# ServoEncoder_Serial.net
KiCad netlist of a schematic drawn in EAGLE
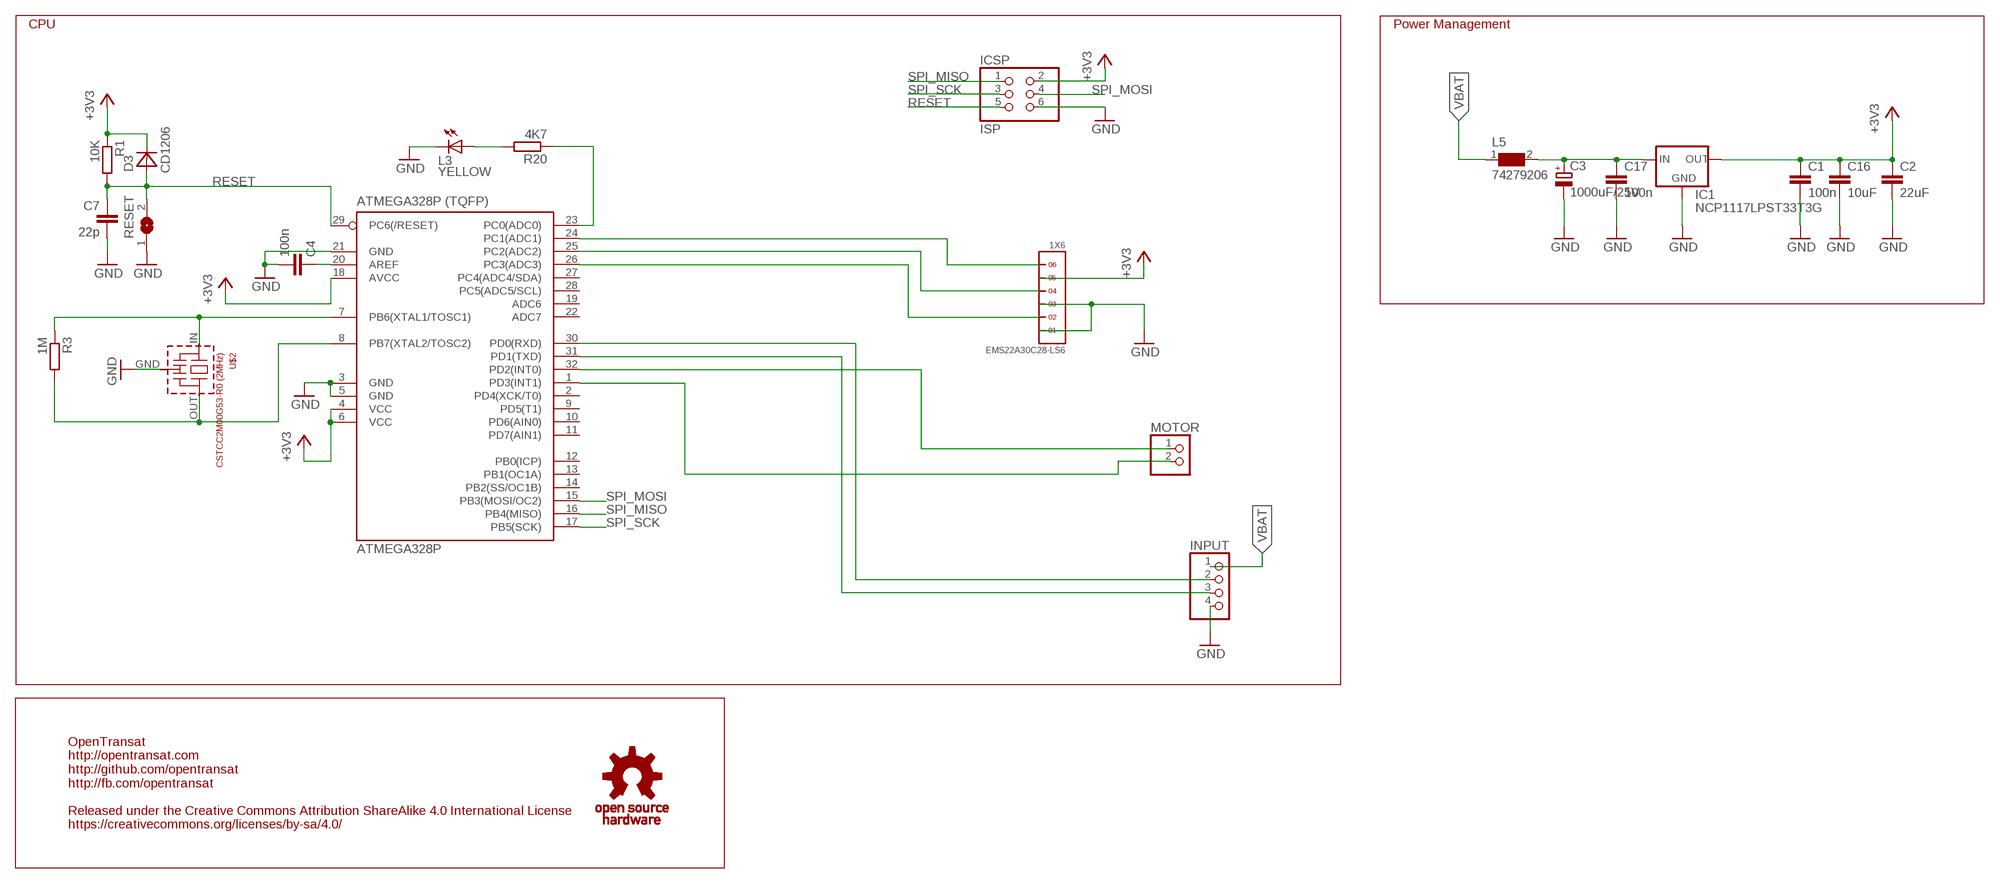
[diagram p0: schematic, sheet 1]

(export (version "E")
  (design (tool "Eeschema 10.0.6"))
  (components
    (comp (ref "ATMEGA328P")
      (value "ATMEGA328P (TQFP)")
      (footprint "eagle-import:TQFP32-08")
      (fields (field (name "MPN") "ATMEGA8-16AU"))
      (libsource (lib "eagle-import") (part "MEGA8-AI"))
    )
    (comp (ref "C1")
      (value "100n")
      (footprint "eagle-import:C0603")
      (libsource (lib "eagle-import") (part "C-EUC0603"))
    )
    (comp (ref "C2")
      (value "22uF")
      (footprint "eagle-import:C1210")
      (libsource (lib "eagle-import") (part "C-EUC1210"))
    )
    (comp (ref "C3")
      (value "1000uF/25V")
      (footprint "eagle-import:E5-10,5")
      (libsource (lib "eagle-import") (part "CPOL-EUE5-10.5"))
    )
    (comp (ref "C4")
      (value "100n")
      (footprint "eagle-import:C0603")
      (libsource (lib "eagle-import") (part "C-EUC0603"))
    )
    (comp (ref "C7")
      (value "22p")
      (footprint "eagle-import:C0603")
      (libsource (lib "eagle-import") (part "C-EUC0603"))
    )
    (comp (ref "C16")
      (value "10uF")
      (footprint "eagle-import:C1206")
      (libsource (lib "eagle-import") (part "C-EUC1206"))
    )
    (comp (ref "C17")
      (value "100n")
      (footprint "eagle-import:C0603")
      (libsource (lib "eagle-import") (part "C-EUC0603"))
    )
    (comp (ref "D3")
      (value "CD1206")
      (footprint "eagle-import:R1206")
      (libsource (lib "eagle-import") (part "CD1206"))
    )
    (comp (ref "EMS22A30C28-LS6")
      (value "1X6")
      (footprint "eagle-import:1X6")
      (libsource (lib "eagle-import") (part "1X6"))
    )
    (comp (ref "IC1")
      (value "NCP1117LPST33T3G")
      (footprint "eagle-import:SOT223")
      (fields (field (name "MF") "Texas Instruments") (field (name "MPN") "LM1117MP-3.3"))
      (libsource (lib "eagle-import") (part "LM1117?-MP3.3"))
    )
    (comp (ref "ICSP")
      (value "ISP")
      (footprint "eagle-import:2X03")
      (libsource (lib "eagle-import") (part "PINHD-2X3"))
    )
    (comp (ref "INPUT")
      (value "PINHD-1X4")
      (footprint "eagle-import:1X04")
      (libsource (lib "eagle-import") (part "PINHD-1X4"))
    )
    (comp (ref "L3")
      (value "YELLOW")
      (footprint "eagle-import:CHIPLED_0805")
      (libsource (lib "eagle-import") (part "LEDCHIPLED_0805"))
    )
    (comp (ref "L5")
      (value "74279206")
      (footprint "eagle-import:0805")
      (libsource (lib "eagle-import") (part "WE-CBF_0805"))
    )
    (comp (ref "MOTOR")
      (value "PINHD-1X2")
      (footprint "eagle-import:1X02")
      (libsource (lib "eagle-import") (part "PINHD-1X2"))
    )
    (comp (ref "R1")
      (value "10K")
      (footprint "eagle-import:R0603")
      (libsource (lib "eagle-import") (part "R-EU_R0603"))
    )
    (comp (ref "R3")
      (value "1M")
      (footprint "eagle-import:R0603")
      (libsource (lib "eagle-import") (part "R-EU_R0603"))
    )
    (comp (ref "R20")
      (value "4K7")
      (footprint "eagle-import:R0603")
      (libsource (lib "eagle-import") (part "R-EU_R0603"))
    )
    (comp (ref "RESET")
      (value "SJW")
      (footprint "eagle-import:SJW")
      (libsource (lib "eagle-import") (part "SJW"))
    )
    (comp (ref "U$1")
      (value "OSHW_S")
      (footprint "eagle-import:OSHWS")
      (libsource (lib "eagle-import") (part "OSHW_S"))
    )
    (comp (ref "U$2")
      (value "CSTCC2M00G53-R0 (2MHz)")
      (footprint "eagle-import:CSTCC")
      (libsource (lib "eagle-import") (part "CSTCC"))
    )
  )
  (nets
    (net (code "1") (name "+3V3") (class "Default")
      (node (ref "ATMEGA328P") (pin "18") (pinfunction "AVCC_18") (pintype "power_in"))
      (node (ref "ATMEGA328P") (pin "4") (pinfunction "VCC_4") (pintype "power_in"))
      (node (ref "ATMEGA328P") (pin "6") (pinfunction "VCC_6") (pintype "power_in"))
      (node (ref "C1") (pin "1") (pinfunction "1_1") (pintype "passive"))
      (node (ref "C16") (pin "1") (pinfunction "1_1") (pintype "passive"))
      (node (ref "C2") (pin "1") (pinfunction "1_1") (pintype "passive"))
      (node (ref "D3") (pin "2") (pinfunction "C_2") (pintype "passive"))
      (node (ref "EMS22A30C28-LS6") (pin "5") (pinfunction "5_5") (pintype "bidirectional"))
      (node (ref "IC1") (pin "2") (pinfunction "OUT_2") (pintype "passive"))
      (node (ref "IC1") (pin "4") (pinfunction "OUT_4") (pintype "passive"))
      (node (ref "ICSP") (pin "2") (pinfunction "2_2") (pintype "passive"))
      (node (ref "R1") (pin "1") (pinfunction "1_1") (pintype "passive"))
    )
    (net (code "2") (name "/RESET") (class "Default")
      (node (ref "ATMEGA328P") (pin "29") (pinfunction "PC6(/RESET)_29") (pintype "bidirectional"))
      (node (ref "C7") (pin "1") (pinfunction "1_1") (pintype "passive"))
      (node (ref "D3") (pin "1") (pinfunction "A_1") (pintype "passive"))
      (node (ref "ICSP") (pin "5") (pinfunction "5_5") (pintype "passive"))
      (node (ref "R1") (pin "2") (pinfunction "2_2") (pintype "passive"))
      (node (ref "RESET") (pin "2") (pinfunction "2_2") (pintype "passive"))
    )
    (net (code "3") (name "/SPI_MISO") (class "Default")
      (node (ref "ATMEGA328P") (pin "16") (pinfunction "PB4(MISO)_16") (pintype "bidirectional"))
      (node (ref "ICSP") (pin "1") (pinfunction "1_1") (pintype "passive"))
    )
    (net (code "4") (name "/SPI_MOSI") (class "Default")
      (node (ref "ATMEGA328P") (pin "15") (pinfunction "PB3(MOSI/OC2)_15") (pintype "bidirectional"))
      (node (ref "ICSP") (pin "4") (pinfunction "4_4") (pintype "passive"))
    )
    (net (code "5") (name "/SPI_SCK") (class "Default")
      (node (ref "ATMEGA328P") (pin "17") (pinfunction "PB5(SCK)_17") (pintype "bidirectional"))
      (node (ref "ICSP") (pin "3") (pinfunction "3_3") (pintype "passive"))
    )
    (net (code "6") (name "GND") (class "Default")
      (node (ref "ATMEGA328P") (pin "21") (pinfunction "GND_21") (pintype "power_in"))
      (node (ref "ATMEGA328P") (pin "3") (pinfunction "GND_3") (pintype "power_in"))
      (node (ref "ATMEGA328P") (pin "5") (pinfunction "GND_5") (pintype "power_in"))
      (node (ref "C1") (pin "2") (pinfunction "2_2") (pintype "passive"))
      (node (ref "C16") (pin "2") (pinfunction "2_2") (pintype "passive"))
      (node (ref "C17") (pin "2") (pinfunction "2_2") (pintype "passive"))
      (node (ref "C2") (pin "2") (pinfunction "2_2") (pintype "passive"))
      (node (ref "C3") (pin "-") (pinfunction "-_-") (pintype "passive"))
      (node (ref "C4") (pin "2") (pinfunction "2_2") (pintype "passive"))
      (node (ref "C7") (pin "2") (pinfunction "2_2") (pintype "passive"))
      (node (ref "EMS22A30C28-LS6") (pin "1") (pinfunction "1_1") (pintype "bidirectional"))
      (node (ref "EMS22A30C28-LS6") (pin "3") (pinfunction "3_3") (pintype "bidirectional"))
      (node (ref "IC1") (pin "1") (pinfunction "GND_1") (pintype "input"))
      (node (ref "ICSP") (pin "6") (pinfunction "6_6") (pintype "passive"))
      (node (ref "INPUT") (pin "4") (pinfunction "4_4") (pintype "passive"))
      (node (ref "L3") (pin "C") (pinfunction "C_C") (pintype "passive"))
      (node (ref "RESET") (pin "1") (pinfunction "1_1") (pintype "passive"))
      (node (ref "U$2") (pin "GND") (pinfunction "GND_GND") (pintype "power_in"))
    )
    (net (code "7") (name "Net-(ATMEGA328P-AREF)") (class "Default")
      (node (ref "ATMEGA328P") (pin "20") (pinfunction "AREF_20") (pintype "passive"))
      (node (ref "C4") (pin "1") (pinfunction "1_1") (pintype "passive"))
    )
    (net (code "8") (name "Net-(ATMEGA328P-PB6(XTAL1{slash}TOSC1))") (class "Default")
      (node (ref "ATMEGA328P") (pin "7") (pinfunction "PB6(XTAL1/TOSC1)_7") (pintype "bidirectional"))
      (node (ref "R3") (pin "1") (pinfunction "1_1") (pintype "passive"))
      (node (ref "U$2") (pin "IN") (pinfunction "IN_IN") (pintype "input"))
    )
    (net (code "9") (name "Net-(ATMEGA328P-PB7(XTAL2{slash}TOSC2))") (class "Default")
      (node (ref "ATMEGA328P") (pin "8") (pinfunction "PB7(XTAL2/TOSC2)_8") (pintype "bidirectional"))
      (node (ref "R3") (pin "2") (pinfunction "2_2") (pintype "passive"))
      (node (ref "U$2") (pin "OUT") (pinfunction "OUT_OUT") (pintype "output"))
    )
    (net (code "10") (name "Net-(ATMEGA328P-PC0(ADC0))") (class "Default")
      (node (ref "ATMEGA328P") (pin "23") (pinfunction "PC0(ADC0)_23") (pintype "bidirectional"))
      (node (ref "R20") (pin "1") (pinfunction "1_1") (pintype "passive"))
    )
    (net (code "11") (name "Net-(ATMEGA328P-PC1(ADC1))") (class "Default")
      (node (ref "ATMEGA328P") (pin "24") (pinfunction "PC1(ADC1)_24") (pintype "bidirectional"))
      (node (ref "EMS22A30C28-LS6") (pin "6") (pinfunction "6_6") (pintype "bidirectional"))
    )
    (net (code "12") (name "Net-(ATMEGA328P-PC2(ADC2))") (class "Default")
      (node (ref "ATMEGA328P") (pin "25") (pinfunction "PC2(ADC2)_25") (pintype "bidirectional"))
      (node (ref "EMS22A30C28-LS6") (pin "4") (pinfunction "4_4") (pintype "bidirectional"))
    )
    (net (code "13") (name "Net-(ATMEGA328P-PC3(ADC3))") (class "Default")
      (node (ref "ATMEGA328P") (pin "26") (pinfunction "PC3(ADC3)_26") (pintype "bidirectional"))
      (node (ref "EMS22A30C28-LS6") (pin "2") (pinfunction "2_2") (pintype "bidirectional"))
    )
    (net (code "14") (name "Net-(ATMEGA328P-PD0(RXD))") (class "Default")
      (node (ref "ATMEGA328P") (pin "30") (pinfunction "PD0(RXD)_30") (pintype "bidirectional"))
      (node (ref "INPUT") (pin "2") (pinfunction "2_2") (pintype "passive"))
    )
    (net (code "15") (name "Net-(ATMEGA328P-PD1(TXD))") (class "Default")
      (node (ref "ATMEGA328P") (pin "31") (pinfunction "PD1(TXD)_31") (pintype "bidirectional"))
      (node (ref "INPUT") (pin "3") (pinfunction "3_3") (pintype "passive"))
    )
    (net (code "16") (name "Net-(ATMEGA328P-PD2(INT0))") (class "Default")
      (node (ref "ATMEGA328P") (pin "32") (pinfunction "PD2(INT0)_32") (pintype "bidirectional"))
      (node (ref "MOTOR") (pin "1") (pinfunction "1_1") (pintype "passive"))
    )
    (net (code "17") (name "Net-(ATMEGA328P-PD3(INT1))") (class "Default")
      (node (ref "ATMEGA328P") (pin "1") (pinfunction "PD3(INT1)_1") (pintype "bidirectional"))
      (node (ref "MOTOR") (pin "2") (pinfunction "2_2") (pintype "passive"))
    )
    (net (code "18") (name "Net-(IC1-IN)") (class "Default")
      (node (ref "C17") (pin "1") (pinfunction "1_1") (pintype "passive"))
      (node (ref "C3") (pin "+") (pinfunction "+_+") (pintype "passive"))
      (node (ref "IC1") (pin "3") (pinfunction "IN_3") (pintype "input"))
      (node (ref "L5") (pin "2") (pinfunction "2_2") (pintype "passive"))
    )
    (net (code "19") (name "Net-(L3-PadA)") (class "Default")
      (node (ref "L3") (pin "A") (pinfunction "A_A") (pintype "passive"))
      (node (ref "R20") (pin "2") (pinfunction "2_2") (pintype "passive"))
    )
    (net (code "20") (name "VBAT") (class "Default")
      (node (ref "INPUT") (pin "1") (pinfunction "1_1") (pintype "passive"))
      (node (ref "L5") (pin "1") (pinfunction "1_1") (pintype "passive"))
    )
    (net (code "21") (name "unconnected-(ATMEGA328P-ADC6-Pad19)") (class "Default")
      (node (ref "ATMEGA328P") (pin "19") (pinfunction "ADC6_19") (pintype "bidirectional"))
    )
    (net (code "22") (name "unconnected-(ATMEGA328P-ADC7-Pad22)") (class "Default")
      (node (ref "ATMEGA328P") (pin "22") (pinfunction "ADC7_22") (pintype "bidirectional"))
    )
    (net (code "23") (name "unconnected-(ATMEGA328P-PB0(ICP)-Pad12)") (class "Default")
      (node (ref "ATMEGA328P") (pin "12") (pinfunction "PB0(ICP)_12") (pintype "bidirectional"))
    )
    (net (code "24") (name "unconnected-(ATMEGA328P-PB1(OC1A)-Pad13)") (class "Default")
      (node (ref "ATMEGA328P") (pin "13") (pinfunction "PB1(OC1A)_13") (pintype "bidirectional"))
    )
    (net (code "25") (name "unconnected-(ATMEGA328P-PB2(SS{slash}OC1B)-Pad14)") (class "Default")
      (node (ref "ATMEGA328P") (pin "14") (pinfunction "PB2(SS/OC1B)_14") (pintype "bidirectional"))
    )
    (net (code "26") (name "unconnected-(ATMEGA328P-PC4(ADC4{slash}SDA)-Pad27)") (class "Default")
      (node (ref "ATMEGA328P") (pin "27") (pinfunction "PC4(ADC4/SDA)_27") (pintype "bidirectional"))
    )
    (net (code "27") (name "unconnected-(ATMEGA328P-PC5(ADC5{slash}SCL)-Pad28)") (class "Default")
      (node (ref "ATMEGA328P") (pin "28") (pinfunction "PC5(ADC5/SCL)_28") (pintype "bidirectional"))
    )
    (net (code "28") (name "unconnected-(ATMEGA328P-PD4(XCK{slash}T0)-Pad2)") (class "Default")
      (node (ref "ATMEGA328P") (pin "2") (pinfunction "PD4(XCK/T0)_2") (pintype "bidirectional"))
    )
    (net (code "29") (name "unconnected-(ATMEGA328P-PD5(T1)-Pad9)") (class "Default")
      (node (ref "ATMEGA328P") (pin "9") (pinfunction "PD5(T1)_9") (pintype "bidirectional"))
    )
    (net (code "30") (name "unconnected-(ATMEGA328P-PD6(AIN0)-Pad10)") (class "Default")
      (node (ref "ATMEGA328P") (pin "10") (pinfunction "PD6(AIN0)_10") (pintype "bidirectional"))
    )
    (net (code "31") (name "unconnected-(ATMEGA328P-PD7(AIN1)-Pad11)") (class "Default")
      (node (ref "ATMEGA328P") (pin "11") (pinfunction "PD7(AIN1)_11") (pintype "bidirectional"))
    )
  )
)
